# CH32F_V208C-R0.net
KiCad netlist of a schematic drawn in Altium Designer
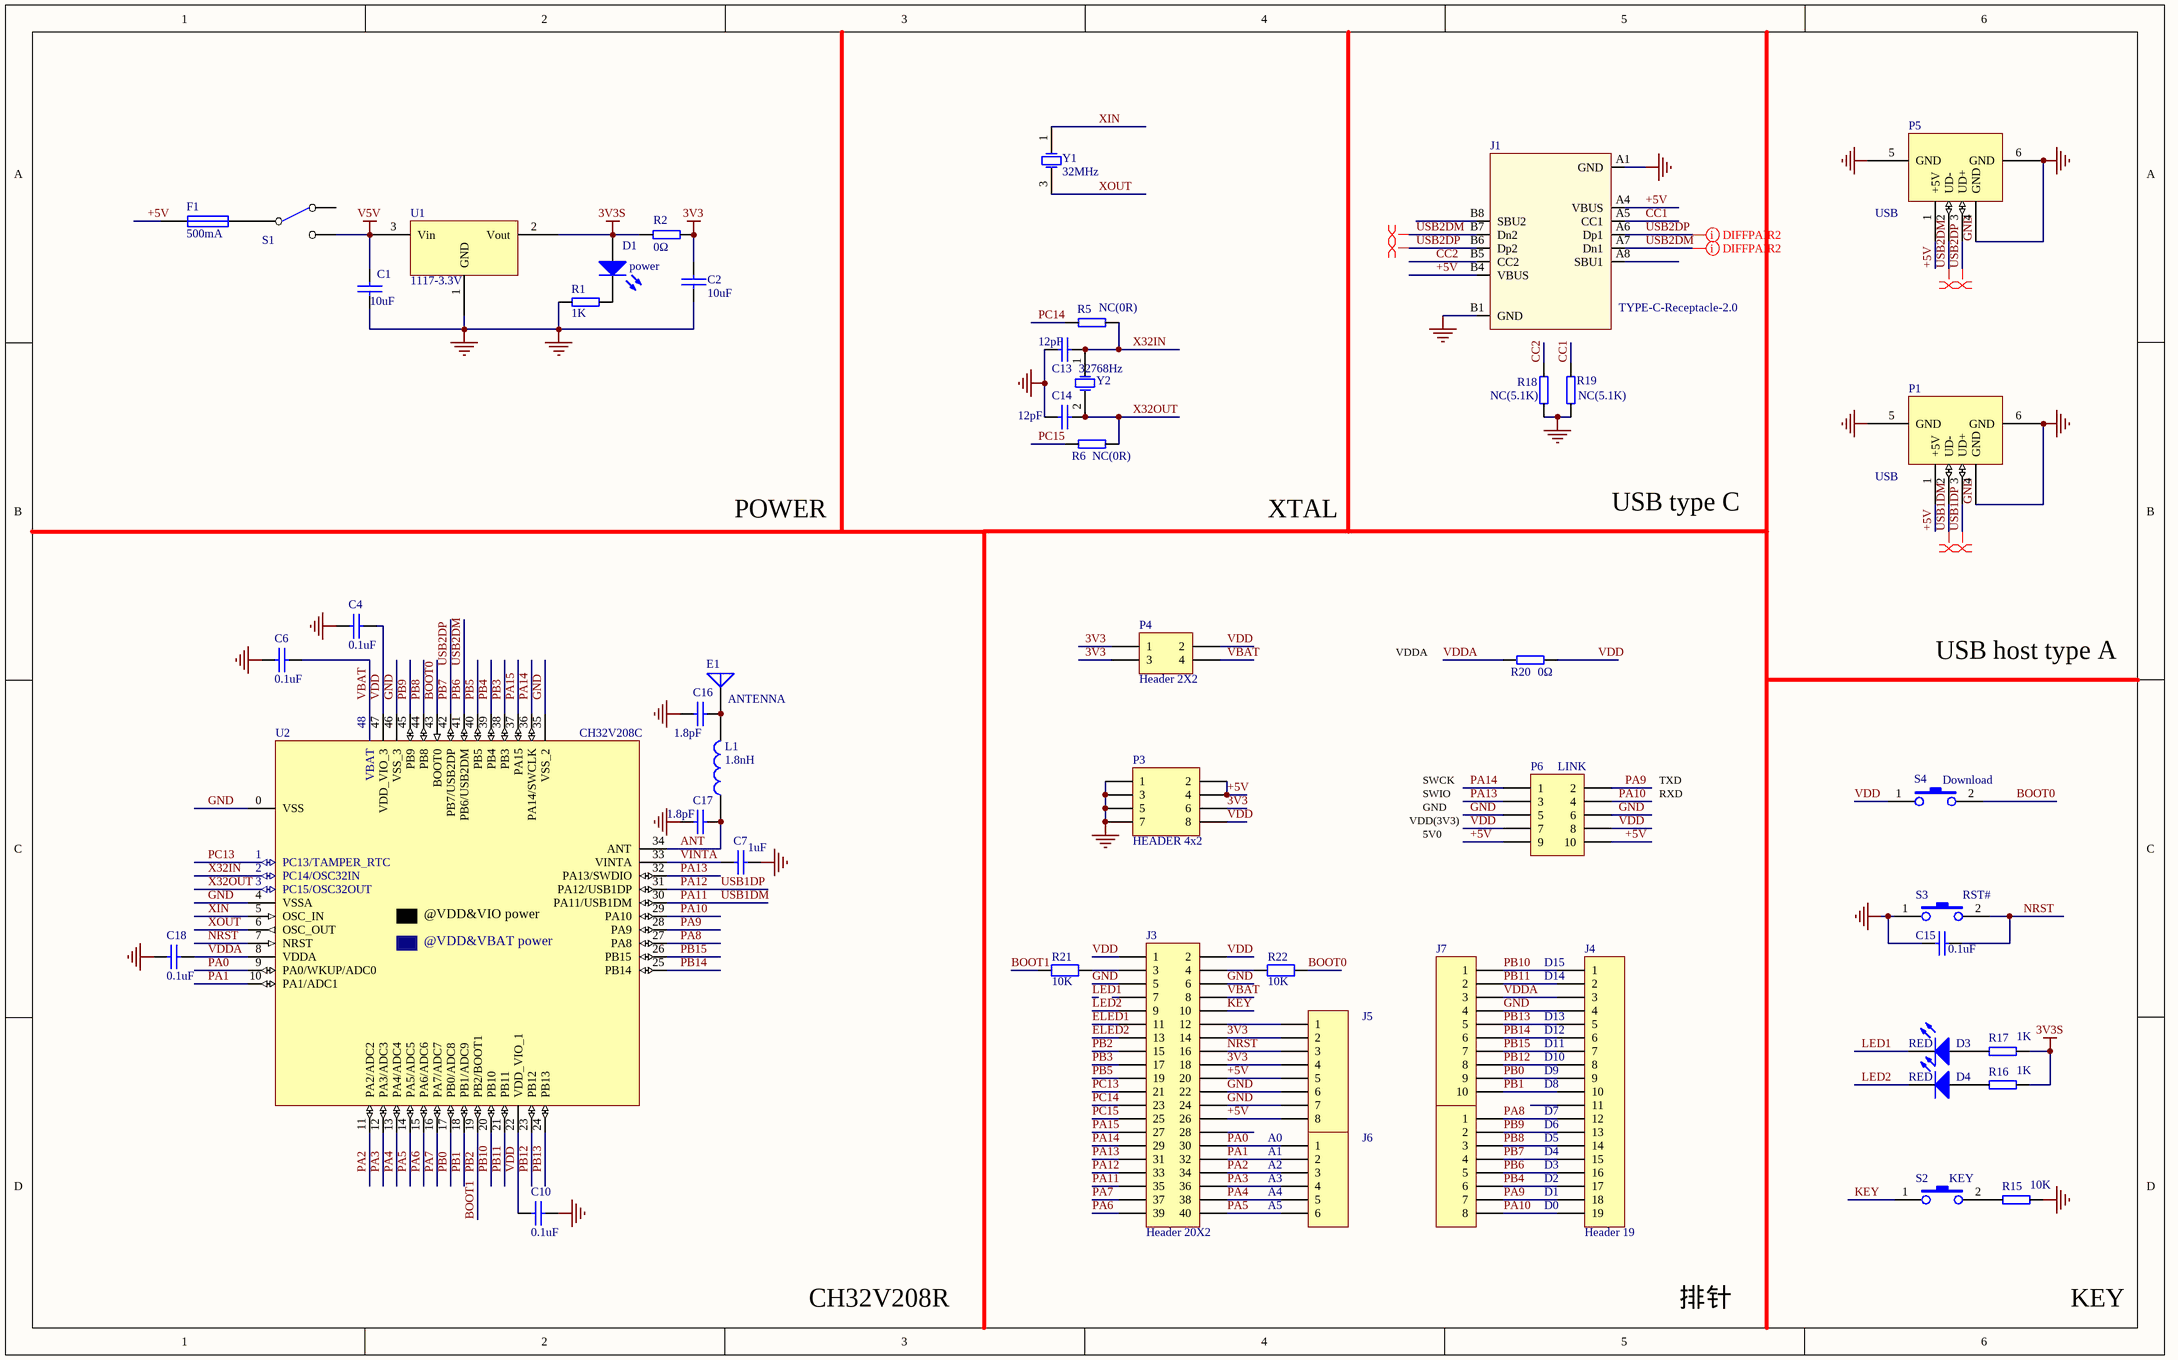
[diagram p0: CH32F&V208C-R0.SchDoc]

(export (version "E")
  (design (tool "Eeschema 10.0.6"))
  (components
    (comp (ref "C1")
      (value "10uF")
      (footprint "3216_C")
      (description "Capacitor")
      (libsource (lib "") (part "CAP_1"))
    )
    (comp (ref "C2")
      (value "10uF")
      (footprint "0603_C")
      (description "Capacitor")
      (libsource (lib "") (part "CAP_1"))
    )
    (comp (ref "C4")
      (value "0.1uF")
      (footprint "0603_C")
      (description "Capacitor")
      (libsource (lib "*") (part "CAP"))
    )
    (comp (ref "C6")
      (value "0.1uF")
      (footprint "0603_C")
      (description "Capacitor")
      (libsource (lib "*") (part "CAP"))
    )
    (comp (ref "C7")
      (value "1uF")
      (footprint "0603_C")
      (description "Capacitor")
      (libsource (lib "*") (part "CAP"))
    )
    (comp (ref "C10")
      (value "0.1uF")
      (footprint "0603_C")
      (description "Capacitor")
      (libsource (lib "*") (part "CAP"))
    )
    (comp (ref "C13")
      (value "12pF")
      (footprint "0603_C")
      (description "Capacitor")
      (libsource (lib "") (part "CAP_1"))
    )
    (comp (ref "C14")
      (value "12pF")
      (footprint "0603_C")
      (description "Capacitor")
      (libsource (lib "") (part "CAP_1"))
    )
    (comp (ref "C15")
      (value "0.1uF")
      (footprint "0603_C")
      (description "Capacitor")
      (libsource (lib "*") (part "CAP"))
    )
    (comp (ref "C16")
      (value "1.8pF")
      (footprint "0603_C")
      (description "Capacitor")
      (libsource (lib "*") (part "CAP"))
    )
    (comp (ref "C17")
      (value "1.8pF")
      (footprint "0603_C")
      (description "Capacitor")
      (libsource (lib "*") (part "CAP"))
    )
    (comp (ref "C18")
      (value "0.1uF")
      (footprint "0603_C")
      (description "Capacitor")
      (libsource (lib "*") (part "CAP"))
    )
    (comp (ref "D1")
      (value "power")
      (footprint "0603+")
      (description "Typical INFRARED GaAs LED")
      (fields (field (name "PUBLISHER") "Altium Limited"))
      (libsource (lib "*") (part "LED0"))
    )
    (comp (ref "D3")
      (value "RED")
      (footprint "0603+")
      (description "Typical INFRARED GaAs LED")
      (fields (field (name "PUBLISHER") "Altium Limited"))
      (libsource (lib "*") (part "LED0"))
    )
    (comp (ref "D4")
      (value "RED")
      (footprint "0603+")
      (description "Typical INFRARED GaAs LED")
      (fields (field (name "PUBLISHER") "Altium Limited"))
      (libsource (lib "*") (part "LED0"))
    )
    (comp (ref "E1")
      (value "ANTENNA")
      (footprint "ANT-F-1-2.4G-1.6mmFR4")
      (description "Generic Antenna")
      (libsource (lib "*") (part "ANTENNA"))
    )
    (comp (ref "F1")
      (value "500mA")
      (footprint "0603")
      (description "Fuse")
      (libsource (lib "wch_sch_others") (part "FUSE1"))
    )
    (comp (ref "J1")
      (value "TYPE-C-Receptacle-2.0")
      (footprint "TYPE-C-Receptacle-2.0")
      (description "Type-C USB2.0 母座")
      (libsource (lib "Miscellaneous SCH Lib") (part "TYPE-C-Receptacle-2.0"))
    )
    (comp (ref "J3")
      (value "Header 20X2")
      (footprint "IDC40-2.54mm")
      (description "Header, 20-Pin, Dual row")
      (fields (field (name "PUBLISHER") "Altium Limited"))
      (libsource (lib "Miscellaneous Connectors") (part "Header 20X2"))
    )
    (comp (ref "J4")
      (value "Header 19")
      (footprint "SIP19-2.54mm")
      (description "Header, 19-Pin")
      (fields (field (name "PUBLISHER") "Altium Limited"))
      (libsource (lib "Miscellaneous Connectors") (part "Header 19"))
    )
    (comp (ref "J5")
      (value "Header 8")
      (footprint "SIP8-2.54mm")
      (description "Header, 8-Pin")
      (fields (field (name "PUBLISHER") "Altium Limited"))
      (libsource (lib "Miscellaneous Connectors") (part "Header 8"))
    )
    (comp (ref "J6")
      (value "Header 6")
      (footprint "SIP6-2.54MM")
      (description "Header, 6-Pin")
      (fields (field (name "PUBLISHER") "Altium Limited"))
      (libsource (lib "Miscellaneous Connectors") (part "Header 6"))
    )
    (comp (ref "J7")
      (value "Header 10")
      (footprint "SIP10-2.54mm")
      (description "Header, 10-Pin")
      (fields (field (name "PUBLISHER") "Altium Limited"))
      (libsource (lib "Miscellaneous Connectors") (part "Header 10"))
    )
    (comp (ref "J8")
      (value "Header 8")
      (footprint "SIP8-2.54mm")
      (description "Header, 8-Pin")
      (fields (field (name "PUBLISHER") "Altium Limited"))
      (libsource (lib "") (part "Header 8_1"))
    )
    (comp (ref "L1") (value "1.8nH") (footprint "0603") (libsource (lib "*") (part "INDUCTOR")))
    (comp (ref "P1")
      (value "USB")
      (footprint "USBAF")
      (description "USB Port")
      (libsource (lib "*") (part "USB"))
    )
    (comp (ref "P3")
      (value "HEADER 4x2")
      (footprint "MYPCB:IDC8-2.54mm")
      (description "Header, 4-Pin, Dual row")
      (libsource (lib "wch_sch_others") (part "HEADER 4x2"))
    )
    (comp (ref "P4")
      (value "Header 2X2")
      (footprint "IDC4-2.54mm")
      (description "Header, 2-Pin, Dual row")
      (fields (field (name "PUBLISHER") "Altium Limited"))
      (libsource (lib "Miscellaneous Connectors") (part "Header 2X2"))
    )
    (comp (ref "P5")
      (value "USB")
      (footprint "USBAF")
      (description "USB Port")
      (libsource (lib "*") (part "USB"))
    )
    (comp (ref "P6")
      (value "LINK")
      (footprint "IDC10-2.54mm")
      (description "Header, 5-Pin, Dual row, Right Angle")
      (fields (field (name "PUBLISHER") "Altium Limited"))
      (libsource (lib "Miscellaneous Connectors") (part "Header 5X2H"))
    )
    (comp (ref "R1") (value "1K") (footprint "0603") (libsource (lib "wch_sch_others") (part "RES")))
    (comp (ref "R2") (value "0Ω") (footprint "0603") (libsource (lib "wch_sch_others") (part "RES")))
    (comp (ref "R5") (value "NC(0R)") (footprint "0603") (libsource (lib "wch_sch_others") (part "RES")))
    (comp (ref "R6") (value "NC(0R)") (footprint "0603") (libsource (lib "wch_sch_others") (part "RES")))
    (comp (ref "R15") (value "10K") (footprint "0603") (libsource (lib "wch_sch_others") (part "RES")))
    (comp (ref "R16") (value "1K") (footprint "0603") (libsource (lib "wch_sch_others") (part "RES")))
    (comp (ref "R17") (value "1K") (footprint "0603") (libsource (lib "wch_sch_others") (part "RES")))
    (comp (ref "R18") (value "NC(5.1K)") (footprint "0603") (libsource (lib "wch_sch_others") (part "RES")))
    (comp (ref "R19") (value "NC(5.1K)") (footprint "0603") (libsource (lib "wch_sch_others") (part "RES")))
    (comp (ref "R20") (value "0Ω") (footprint "0603") (libsource (lib "*") (part "R")))
    (comp (ref "R21")
      (value "10K")
      (footprint "0603")
      (description "Resistor")
      (libsource (lib "Miscellaneous Devices") (part "Res2"))
    )
    (comp (ref "R22")
      (value "10K")
      (footprint "0603")
      (description "Resistor")
      (libsource (lib "Miscellaneous Devices") (part "Res2"))
    )
    (comp (ref "S1") (value "SW SPDT") (footprint "SW1") (libsource (lib "*") (part "SW SPDT")))
    (comp (ref "S2")
      (value "KEY")
      (footprint "SMD_6.1x3.65x2.5mm-KEY")
      (libsource (lib "wch_sch_others") (part "KEY1"))
    )
    (comp (ref "S3")
      (value "RST#")
      (footprint "SMD_6.1x3.65x2.5mm-KEY")
      (libsource (lib "wch_sch_others") (part "KEY1"))
    )
    (comp (ref "S4")
      (value "Download")
      (footprint "SMD_6.1x3.65x2.5mm-KEY")
      (libsource (lib "wch_sch_others") (part "KEY1"))
    )
    (comp (ref "U1")
      (value "1117-3.3V")
      (footprint "SOT-223")
      (libsource (lib "wch_sch_others") (part "1117-3.3V"))
    )
    (comp (ref "U2")
      (value "CH32V208C")
      (footprint "QFN48_5x5")
      (description "RISC-V BLE5.3 MCU, 10M Ethernet, 2*USB, CAN")
      (libsource (lib "CHXXX") (part "CH32V208C"))
    )
    (comp (ref "Y1")
      (value "32MHz")
      (footprint "XT3225")
      (description "Crystal Oscillator")
      (fields (field (name "PUBLISHER") "Altium Limited"))
      (libsource (lib "") (part "XTAL_1"))
    )
    (comp (ref "Y2")
      (value "32768Hz")
      (footprint "FC-135")
      (description "Crystal Oscillator")
      (fields (field (name "PUBLISHER") "Altium Limited"))
      (libsource (lib "*") (part "XTAL"))
    )
  )
  (nets
    (net (code "1") (name "/+5V") (class "Default")
      (node (ref "F1") (pin "1") (pinfunction "1_1") (pintype "passive"))
      (node (ref "J1") (pin "A4") (pinfunction "VBUS_A4") (pintype "passive"))
      (node (ref "J1") (pin "B4") (pinfunction "VBUS_B4") (pintype "passive"))
      (node (ref "J3") (pin "20") (pinfunction "20_20") (pintype "passive"))
      (node (ref "J3") (pin "26") (pinfunction "26_26") (pintype "passive"))
      (node (ref "J5") (pin "5") (pinfunction "5_5") (pintype "passive"))
      (node (ref "J5") (pin "8") (pinfunction "8_8") (pintype "passive"))
      (node (ref "P1") (pin "1") (pinfunction "+5V_1") (pintype "power_in"))
      (node (ref "P3") (pin "2") (pinfunction "2_2") (pintype "passive"))
      (node (ref "P3") (pin "4") (pinfunction "4_4") (pintype "passive"))
      (node (ref "P5") (pin "1") (pinfunction "+5V_1") (pintype "power_in"))
      (node (ref "P6") (pin "10") (pinfunction "10_10") (pintype "passive"))
      (node (ref "P6") (pin "9") (pinfunction "9_9") (pintype "passive"))
    )
    (net (code "2") (name "/ANT") (class "Default")
      (node (ref "C17") (pin "2") (pinfunction "2_2") (pintype "passive"))
      (node (ref "L1") (pin "1") (pinfunction "1_1") (pintype "passive"))
      (node (ref "U2") (pin "34") (pinfunction "ANT_34") (pintype "power_in"))
    )
    (net (code "3") (name "/BOOT0") (class "Default")
      (node (ref "R22") (pin "2") (pinfunction "2_2") (pintype "passive"))
      (node (ref "S4") (pin "2") (pinfunction "2_2") (pintype "passive"))
      (node (ref "U2") (pin "43") (pinfunction "BOOT0_43") (pintype "input"))
    )
    (net (code "4") (name "/BOOT1") (class "Default")
      (node (ref "J3") (pin "15") (pinfunction "15_15") (pintype "passive"))
      (node (ref "R21") (pin "1") (pinfunction "1_1") (pintype "passive"))
      (node (ref "U2") (pin "19") (pinfunction "PB2/BOOT1_19") (pintype "bidirectional"))
    )
    (net (code "5") (name "/CC1") (class "Default")
      (node (ref "J1") (pin "A5") (pinfunction "CC1_A5") (pintype "passive"))
      (node (ref "R19") (pin "1") (pintype "passive"))
    )
    (net (code "6") (name "/CC2") (class "Default")
      (node (ref "J1") (pin "B5") (pinfunction "CC2_B5") (pintype "passive"))
      (node (ref "R18") (pin "1") (pintype "passive"))
    )
    (net (code "7") (name "/ELED1") (class "Default")
      (node (ref "J3") (pin "11") (pinfunction "11_11") (pintype "passive"))
    )
    (net (code "8") (name "/ELED2") (class "Default")
      (node (ref "J3") (pin "13") (pinfunction "13_13") (pintype "passive"))
    )
    (net (code "9") (name "/KEY") (class "Default")
      (node (ref "J3") (pin "10") (pinfunction "10_10") (pintype "passive"))
      (node (ref "S2") (pin "1") (pinfunction "1_1") (pintype "passive"))
    )
    (net (code "10") (name "/LED1") (class "Default")
      (node (ref "D3") (pin "2") (pinfunction "K_2") (pintype "passive"))
    )
    (net (code "11") (name "/LED2") (class "Default")
      (node (ref "D4") (pin "2") (pinfunction "K_2") (pintype "passive"))
      (node (ref "J3") (pin "9") (pinfunction "9_9") (pintype "passive"))
    )
    (net (code "12") (name "/NRST") (class "Default")
      (node (ref "C15") (pin "2") (pinfunction "2_2") (pintype "passive"))
      (node (ref "J3") (pin "16") (pinfunction "16_16") (pintype "passive"))
      (node (ref "J5") (pin "3") (pinfunction "3_3") (pintype "passive"))
      (node (ref "S3") (pin "2") (pinfunction "2_2") (pintype "passive"))
      (node (ref "U2") (pin "7") (pinfunction "NRST_7") (pintype "input"))
    )
    (net (code "13") (name "/PA0") (class "Default")
      (node (ref "J3") (pin "30") (pinfunction "30_30") (pintype "passive"))
      (node (ref "J6") (pin "1") (pinfunction "1_1") (pintype "passive"))
      (node (ref "U2") (pin "9") (pinfunction "PA0/WKUP/ADC0_9") (pintype "bidirectional"))
    )
    (net (code "14") (name "/PA1") (class "Default")
      (node (ref "J3") (pin "32") (pinfunction "32_32") (pintype "passive"))
      (node (ref "J6") (pin "2") (pinfunction "2_2") (pintype "passive"))
      (node (ref "U2") (pin "10") (pinfunction "PA1/ADC1_10") (pintype "bidirectional"))
    )
    (net (code "15") (name "/PA2") (class "Default")
      (node (ref "J3") (pin "34") (pinfunction "34_34") (pintype "passive"))
      (node (ref "J6") (pin "3") (pinfunction "3_3") (pintype "passive"))
      (node (ref "U2") (pin "11") (pinfunction "PA2/ADC2_11") (pintype "bidirectional"))
    )
    (net (code "16") (name "/PA3") (class "Default")
      (node (ref "J3") (pin "36") (pinfunction "36_36") (pintype "passive"))
      (node (ref "J6") (pin "4") (pinfunction "4_4") (pintype "passive"))
      (node (ref "U2") (pin "12") (pinfunction "PA3/ADC3_12") (pintype "bidirectional"))
    )
    (net (code "17") (name "/PA4") (class "Default")
      (node (ref "J3") (pin "38") (pinfunction "38_38") (pintype "passive"))
      (node (ref "J6") (pin "5") (pinfunction "5_5") (pintype "passive"))
      (node (ref "U2") (pin "13") (pinfunction "PA4/ADC4_13") (pintype "bidirectional"))
    )
    (net (code "18") (name "/PA5") (class "Default")
      (node (ref "J3") (pin "40") (pinfunction "40_40") (pintype "passive"))
      (node (ref "J6") (pin "6") (pinfunction "6_6") (pintype "passive"))
      (node (ref "U2") (pin "14") (pinfunction "PA5/ADC5_14") (pintype "bidirectional"))
    )
    (net (code "19") (name "/PA6") (class "Default")
      (node (ref "J3") (pin "39") (pinfunction "39_39") (pintype "passive"))
      (node (ref "U2") (pin "15") (pinfunction "PA6/ADC6_15") (pintype "bidirectional"))
    )
    (net (code "20") (name "/PA7") (class "Default")
      (node (ref "J3") (pin "37") (pinfunction "37_37") (pintype "passive"))
      (node (ref "U2") (pin "16") (pinfunction "PA7/ADC7_16") (pintype "bidirectional"))
    )
    (net (code "21") (name "/PA8") (class "Default")
      (node (ref "J4") (pin "12") (pinfunction "12_12") (pintype "passive"))
      (node (ref "J8") (pin "1") (pinfunction "1_1") (pintype "passive"))
      (node (ref "U2") (pin "27") (pinfunction "PA8_27") (pintype "bidirectional"))
    )
    (net (code "22") (name "/PA9") (class "Default")
      (node (ref "J4") (pin "18") (pinfunction "18_18") (pintype "passive"))
      (node (ref "J8") (pin "7") (pinfunction "7_7") (pintype "passive"))
      (node (ref "P6") (pin "2") (pinfunction "2_2") (pintype "passive"))
      (node (ref "U2") (pin "28") (pinfunction "PA9_28") (pintype "bidirectional"))
    )
    (net (code "23") (name "/PA10") (class "Default")
      (node (ref "J4") (pin "19") (pinfunction "19_19") (pintype "passive"))
      (node (ref "J8") (pin "8") (pinfunction "8_8") (pintype "passive"))
      (node (ref "P6") (pin "4") (pinfunction "4_4") (pintype "passive"))
      (node (ref "U2") (pin "29") (pinfunction "PA10_29") (pintype "bidirectional"))
    )
    (net (code "24") (name "/PA11") (class "Default")
      (node (ref "J3") (pin "35") (pinfunction "35_35") (pintype "passive"))
      (node (ref "P1") (pin "2") (pinfunction "UD-_2") (pintype "bidirectional"))
      (node (ref "U2") (pin "30") (pinfunction "PA11/USB1DM_30") (pintype "bidirectional"))
    )
    (net (code "25") (name "/PA12") (class "Default")
      (node (ref "J3") (pin "33") (pinfunction "33_33") (pintype "passive"))
      (node (ref "P1") (pin "3") (pinfunction "UD+_3") (pintype "bidirectional"))
      (node (ref "U2") (pin "31") (pinfunction "PA12/USB1DP_31") (pintype "bidirectional"))
    )
    (net (code "26") (name "/PA13") (class "Default")
      (node (ref "J3") (pin "31") (pinfunction "31_31") (pintype "passive"))
      (node (ref "P6") (pin "3") (pinfunction "3_3") (pintype "passive"))
      (node (ref "U2") (pin "32") (pinfunction "PA13/SWDIO_32") (pintype "bidirectional"))
    )
    (net (code "27") (name "/PA14") (class "Default")
      (node (ref "J3") (pin "29") (pinfunction "29_29") (pintype "passive"))
      (node (ref "P6") (pin "1") (pinfunction "1_1") (pintype "passive"))
      (node (ref "U2") (pin "36") (pinfunction "PA14/SWCLK_36") (pintype "bidirectional"))
    )
    (net (code "28") (name "/PA15") (class "Default")
      (node (ref "J3") (pin "27") (pinfunction "27_27") (pintype "passive"))
      (node (ref "U2") (pin "37") (pinfunction "PA15_37") (pintype "bidirectional"))
    )
    (net (code "29") (name "/PB0") (class "Default")
      (node (ref "J4") (pin "9") (pinfunction "9_9") (pintype "passive"))
      (node (ref "J7") (pin "9") (pinfunction "9_9") (pintype "passive"))
      (node (ref "U2") (pin "17") (pinfunction "PB0/ADC8_17") (pintype "bidirectional"))
    )
    (net (code "30") (name "/PB1") (class "Default")
      (node (ref "J4") (pin "10") (pinfunction "10_10") (pintype "passive"))
      (node (ref "J7") (pin "10") (pinfunction "10_10") (pintype "passive"))
      (node (ref "U2") (pin "18") (pinfunction "PB1/ADC9_18") (pintype "bidirectional"))
    )
    (net (code "31") (name "/PB3") (class "Default")
      (node (ref "J3") (pin "17") (pinfunction "17_17") (pintype "passive"))
      (node (ref "U2") (pin "38") (pinfunction "PB3_38") (pintype "bidirectional"))
    )
    (net (code "32") (name "/PB4") (class "Default")
      (node (ref "J4") (pin "17") (pinfunction "17_17") (pintype "passive"))
      (node (ref "J8") (pin "6") (pinfunction "6_6") (pintype "passive"))
      (node (ref "U2") (pin "39") (pinfunction "PB4_39") (pintype "bidirectional"))
    )
    (net (code "33") (name "/PB5") (class "Default")
      (node (ref "J3") (pin "19") (pinfunction "19_19") (pintype "passive"))
      (node (ref "U2") (pin "40") (pinfunction "PB5_40") (pintype "bidirectional"))
    )
    (net (code "34") (name "/PB6") (class "Default")
      (node (ref "J1") (pin "A7") (pinfunction "Dn1_A7") (pintype "passive"))
      (node (ref "J1") (pin "B7") (pinfunction "Dn2_B7") (pintype "passive"))
      (node (ref "J4") (pin "16") (pinfunction "16_16") (pintype "passive"))
      (node (ref "J8") (pin "5") (pinfunction "5_5") (pintype "passive"))
      (node (ref "P5") (pin "2") (pinfunction "UD-_2") (pintype "bidirectional"))
      (node (ref "U2") (pin "41") (pinfunction "PB6/USB2DM_41") (pintype "bidirectional"))
    )
    (net (code "35") (name "/PB7") (class "Default")
      (node (ref "J1") (pin "A6") (pinfunction "Dp1_A6") (pintype "passive"))
      (node (ref "J1") (pin "B6") (pinfunction "Dp2_B6") (pintype "passive"))
      (node (ref "J4") (pin "15") (pinfunction "15_15") (pintype "passive"))
      (node (ref "J8") (pin "4") (pinfunction "4_4") (pintype "passive"))
      (node (ref "P5") (pin "3") (pinfunction "UD+_3") (pintype "bidirectional"))
      (node (ref "U2") (pin "42") (pinfunction "PB7/USB2DP_42") (pintype "bidirectional"))
    )
    (net (code "36") (name "/PB8") (class "Default")
      (node (ref "J4") (pin "14") (pinfunction "14_14") (pintype "passive"))
      (node (ref "J8") (pin "3") (pinfunction "3_3") (pintype "passive"))
      (node (ref "U2") (pin "44") (pinfunction "PB8_44") (pintype "bidirectional"))
    )
    (net (code "37") (name "/PB9") (class "Default")
      (node (ref "J4") (pin "13") (pinfunction "13_13") (pintype "passive"))
      (node (ref "J8") (pin "2") (pinfunction "2_2") (pintype "passive"))
      (node (ref "U2") (pin "45") (pinfunction "PB9_45") (pintype "bidirectional"))
    )
    (net (code "38") (name "/PB10") (class "Default")
      (node (ref "J4") (pin "1") (pinfunction "1_1") (pintype "passive"))
      (node (ref "J7") (pin "1") (pinfunction "1_1") (pintype "passive"))
      (node (ref "U2") (pin "20") (pinfunction "PB10_20") (pintype "bidirectional"))
    )
    (net (code "39") (name "/PB11") (class "Default")
      (node (ref "J4") (pin "2") (pinfunction "2_2") (pintype "passive"))
      (node (ref "J7") (pin "2") (pinfunction "2_2") (pintype "passive"))
      (node (ref "U2") (pin "21") (pinfunction "PB11_21") (pintype "bidirectional"))
    )
    (net (code "40") (name "/PB12") (class "Default")
      (node (ref "J4") (pin "8") (pinfunction "8_8") (pintype "passive"))
      (node (ref "J7") (pin "8") (pinfunction "8_8") (pintype "passive"))
      (node (ref "U2") (pin "23") (pinfunction "PB12_23") (pintype "bidirectional"))
    )
    (net (code "41") (name "/PB13") (class "Default")
      (node (ref "J4") (pin "5") (pinfunction "5_5") (pintype "passive"))
      (node (ref "J7") (pin "5") (pinfunction "5_5") (pintype "passive"))
      (node (ref "U2") (pin "24") (pinfunction "PB13_24") (pintype "bidirectional"))
    )
    (net (code "42") (name "/PB14") (class "Default")
      (node (ref "J4") (pin "6") (pinfunction "6_6") (pintype "passive"))
      (node (ref "J7") (pin "6") (pinfunction "6_6") (pintype "passive"))
      (node (ref "U2") (pin "25") (pinfunction "PB14_25") (pintype "bidirectional"))
    )
    (net (code "43") (name "/PB15") (class "Default")
      (node (ref "J4") (pin "7") (pinfunction "7_7") (pintype "passive"))
      (node (ref "J7") (pin "7") (pinfunction "7_7") (pintype "passive"))
      (node (ref "U2") (pin "26") (pinfunction "PB15_26") (pintype "bidirectional"))
    )
    (net (code "44") (name "/PC13") (class "Default")
      (node (ref "J3") (pin "21") (pinfunction "21_21") (pintype "passive"))
      (node (ref "U2") (pin "1") (pinfunction "PC13/TAMPER_RTC_1") (pintype "bidirectional"))
    )
    (net (code "45") (name "/PC14") (class "Default")
      (node (ref "J3") (pin "23") (pinfunction "23_23") (pintype "passive"))
      (node (ref "R5") (pin "1") (pintype "passive"))
    )
    (net (code "46") (name "/PC15") (class "Default")
      (node (ref "J3") (pin "25") (pinfunction "25_25") (pintype "passive"))
      (node (ref "R6") (pin "1") (pintype "passive"))
    )
    (net (code "47") (name "/VBAT") (class "Default")
      (node (ref "C6") (pin "1") (pinfunction "1_1") (pintype "passive"))
      (node (ref "J3") (pin "8") (pinfunction "8_8") (pintype "passive"))
      (node (ref "P4") (pin "4") (pinfunction "4_4") (pintype "passive"))
      (node (ref "U2") (pin "48") (pinfunction "VBAT_48") (pintype "power_in"))
    )
    (net (code "48") (name "/VDD") (class "Default")
      (node (ref "C10") (pin "2") (pinfunction "2_2") (pintype "passive"))
      (node (ref "C4") (pin "1") (pinfunction "1_1") (pintype "passive"))
      (node (ref "J3") (pin "1") (pinfunction "1_1") (pintype "passive"))
      (node (ref "J3") (pin "2") (pinfunction "2_2") (pintype "passive"))
      (node (ref "P3") (pin "8") (pinfunction "8_8") (pintype "passive"))
      (node (ref "P4") (pin "2") (pinfunction "2_2") (pintype "passive"))
      (node (ref "P6") (pin "7") (pinfunction "7_7") (pintype "passive"))
      (node (ref "P6") (pin "8") (pinfunction "8_8") (pintype "passive"))
      (node (ref "R20") (pin "1") (pinfunction "1_1") (pintype "passive"))
      (node (ref "S4") (pin "1") (pinfunction "1_1") (pintype "passive"))
      (node (ref "U2") (pin "22") (pinfunction "VDD_VIO_1_22") (pintype "power_in"))
      (node (ref "U2") (pin "47") (pinfunction "VDD_VIO_3_47") (pintype "power_in"))
    )
    (net (code "49") (name "/VDDA") (class "Default")
      (node (ref "C18") (pin "1") (pinfunction "1_1") (pintype "passive"))
      (node (ref "J4") (pin "3") (pinfunction "3_3") (pintype "passive"))
      (node (ref "J7") (pin "3") (pinfunction "3_3") (pintype "passive"))
      (node (ref "R20") (pin "2") (pinfunction "2_2") (pintype "passive"))
      (node (ref "U2") (pin "8") (pinfunction "VDDA_8") (pintype "power_in"))
    )
    (net (code "50") (name "/VINTA") (class "Default")
      (node (ref "C7") (pin "1") (pinfunction "1_1") (pintype "passive"))
      (node (ref "U2") (pin "33") (pinfunction "VINTA_33") (pintype "power_in"))
    )
    (net (code "51") (name "/X32IN") (class "Default")
      (node (ref "C13") (pin "2") (pinfunction "2_2") (pintype "passive"))
      (node (ref "R5") (pin "2") (pintype "passive"))
      (node (ref "U2") (pin "2") (pinfunction "PC14/OSC32IN_2") (pintype "bidirectional"))
      (node (ref "Y2") (pin "1") (pinfunction "OSC1_1") (pintype "passive"))
    )
    (net (code "52") (name "/X32OUT") (class "Default")
      (node (ref "C14") (pin "2") (pinfunction "2_2") (pintype "passive"))
      (node (ref "R6") (pin "2") (pintype "passive"))
      (node (ref "U2") (pin "3") (pinfunction "PC15/OSC32OUT_3") (pintype "bidirectional"))
      (node (ref "Y2") (pin "2") (pinfunction "OSC2_2") (pintype "passive"))
    )
    (net (code "53") (name "/XIN") (class "Default")
      (node (ref "U2") (pin "5") (pinfunction "OSC_IN_5") (pintype "input"))
      (node (ref "Y1") (pin "1") (pinfunction "OSC1_1") (pintype "passive"))
    )
    (net (code "54") (name "/XOUT") (class "Default")
      (node (ref "U2") (pin "6") (pinfunction "OSC_OUT_6") (pintype "output"))
      (node (ref "Y1") (pin "3") (pinfunction "OSC2_3") (pintype "passive"))
    )
    (net (code "55") (name "3V3") (class "Default")
      (node (ref "C2") (pin "1") (pinfunction "1_1") (pintype "passive"))
      (node (ref "J3") (pin "14") (pinfunction "14_14") (pintype "passive"))
      (node (ref "J3") (pin "18") (pinfunction "18_18") (pintype "passive"))
      (node (ref "J5") (pin "2") (pinfunction "2_2") (pintype "passive"))
      (node (ref "J5") (pin "4") (pinfunction "4_4") (pintype "passive"))
      (node (ref "P3") (pin "6") (pinfunction "6_6") (pintype "passive"))
      (node (ref "P4") (pin "1") (pinfunction "1_1") (pintype "passive"))
      (node (ref "P4") (pin "3") (pinfunction "3_3") (pintype "passive"))
      (node (ref "R2") (pin "1") (pintype "passive"))
    )
    (net (code "56") (name "3V3S") (class "Default")
      (node (ref "D1") (pin "1") (pinfunction "A_1") (pintype "passive"))
      (node (ref "R16") (pin "1") (pintype "passive"))
      (node (ref "R17") (pin "1") (pintype "passive"))
      (node (ref "R2") (pin "2") (pintype "passive"))
      (node (ref "U1") (pin "2") (pinfunction "Vout_2") (pintype "passive"))
    )
    (net (code "57") (name "GND") (class "Default")
      (node (ref "C1") (pin "2") (pinfunction "2_2") (pintype "passive"))
      (node (ref "C10") (pin "1") (pinfunction "1_1") (pintype "passive"))
      (node (ref "C13") (pin "1") (pinfunction "1_1") (pintype "passive"))
      (node (ref "C14") (pin "1") (pinfunction "1_1") (pintype "passive"))
      (node (ref "C15") (pin "1") (pinfunction "1_1") (pintype "passive"))
      (node (ref "C16") (pin "1") (pinfunction "1_1") (pintype "passive"))
      (node (ref "C17") (pin "1") (pinfunction "1_1") (pintype "passive"))
      (node (ref "C18") (pin "2") (pinfunction "2_2") (pintype "passive"))
      (node (ref "C2") (pin "2") (pinfunction "2_2") (pintype "passive"))
      (node (ref "C4") (pin "2") (pinfunction "2_2") (pintype "passive"))
      (node (ref "C6") (pin "2") (pinfunction "2_2") (pintype "passive"))
      (node (ref "C7") (pin "2") (pinfunction "2_2") (pintype "passive"))
      (node (ref "J1") (pin "A1") (pinfunction "GND_A1") (pintype "passive"))
      (node (ref "J1") (pin "B1") (pinfunction "GND_B1") (pintype "passive"))
      (node (ref "J3") (pin "22") (pinfunction "22_22") (pintype "passive"))
      (node (ref "J3") (pin "24") (pinfunction "24_24") (pintype "passive"))
      (node (ref "J3") (pin "5") (pinfunction "5_5") (pintype "passive"))
      (node (ref "J3") (pin "6") (pinfunction "6_6") (pintype "passive"))
      (node (ref "J4") (pin "4") (pinfunction "4_4") (pintype "passive"))
      (node (ref "J5") (pin "6") (pinfunction "6_6") (pintype "passive"))
      (node (ref "J5") (pin "7") (pinfunction "7_7") (pintype "passive"))
      (node (ref "J7") (pin "4") (pinfunction "4_4") (pintype "passive"))
      (node (ref "P1") (pin "4") (pinfunction "GND_4") (pintype "power_in"))
      (node (ref "P1") (pin "5") (pinfunction "GND_5") (pintype "power_in"))
      (node (ref "P1") (pin "6") (pinfunction "GND_6") (pintype "power_in"))
      (node (ref "P3") (pin "1") (pinfunction "1_1") (pintype "passive"))
      (node (ref "P3") (pin "3") (pinfunction "3_3") (pintype "passive"))
      (node (ref "P3") (pin "5") (pinfunction "5_5") (pintype "passive"))
      (node (ref "P3") (pin "7") (pinfunction "7_7") (pintype "passive"))
      (node (ref "P5") (pin "4") (pinfunction "GND_4") (pintype "power_in"))
      (node (ref "P5") (pin "5") (pinfunction "GND_5") (pintype "power_in"))
      (node (ref "P5") (pin "6") (pinfunction "GND_6") (pintype "power_in"))
      (node (ref "P6") (pin "5") (pinfunction "5_5") (pintype "passive"))
      (node (ref "P6") (pin "6") (pinfunction "6_6") (pintype "passive"))
      (node (ref "R1") (pin "1") (pintype "passive"))
      (node (ref "R15") (pin "1") (pintype "passive"))
      (node (ref "R18") (pin "2") (pintype "passive"))
      (node (ref "R19") (pin "2") (pintype "passive"))
      (node (ref "S3") (pin "1") (pinfunction "1_1") (pintype "passive"))
      (node (ref "U1") (pin "1") (pinfunction "GND_1") (pintype "passive"))
      (node (ref "U2") (pin "0") (pinfunction "VSS_0") (pintype "power_in"))
      (node (ref "U2") (pin "35") (pinfunction "VSS_2_35") (pintype "power_in"))
      (node (ref "U2") (pin "4") (pinfunction "VSSA_4") (pintype "power_in"))
      (node (ref "U2") (pin "46") (pinfunction "VSS_3_46") (pintype "power_in"))
    )
    (net (code "58") (name "Net-(D1-K)") (class "Default")
      (node (ref "D1") (pin "2") (pinfunction "K_2") (pintype "passive"))
      (node (ref "R1") (pin "2") (pintype "passive"))
    )
    (net (code "59") (name "Net-(D3-A)") (class "Default")
      (node (ref "D3") (pin "1") (pinfunction "A_1") (pintype "passive"))
      (node (ref "R17") (pin "2") (pintype "passive"))
    )
    (net (code "60") (name "Net-(D4-A)") (class "Default")
      (node (ref "D4") (pin "1") (pinfunction "A_1") (pintype "passive"))
      (node (ref "R16") (pin "2") (pintype "passive"))
    )
    (net (code "61") (name "Net-(E1-A)") (class "Default")
      (node (ref "C16") (pin "2") (pinfunction "2_2") (pintype "passive"))
      (node (ref "E1") (pin "1") (pinfunction "A_1") (pintype "passive"))
      (node (ref "L1") (pin "2") (pinfunction "2_2") (pintype "passive"))
    )
    (net (code "62") (name "Net-(J3-Pad3)") (class "Default")
      (node (ref "J3") (pin "3") (pinfunction "3_3") (pintype "passive"))
      (node (ref "R21") (pin "2") (pinfunction "2_2") (pintype "passive"))
    )
    (net (code "63") (name "Net-(J3-Pad4)") (class "Default")
      (node (ref "J3") (pin "4") (pinfunction "4_4") (pintype "passive"))
      (node (ref "R22") (pin "1") (pinfunction "1_1") (pintype "passive"))
    )
    (net (code "64") (name "Net-(J3-Pad12)") (class "Default")
      (node (ref "J3") (pin "12") (pinfunction "12_12") (pintype "passive"))
      (node (ref "J5") (pin "1") (pinfunction "1_1") (pintype "passive"))
    )
    (net (code "65") (name "Net-(R15-Pad2)") (class "Default")
      (node (ref "R15") (pin "2") (pintype "passive"))
      (node (ref "S2") (pin "2") (pinfunction "2_2") (pintype "passive"))
    )
    (net (code "66") (name "Net-(S1-COMMON)") (class "Default")
      (node (ref "F1") (pin "2") (pinfunction "2_2") (pintype "passive"))
      (node (ref "S1") (pin "1") (pinfunction "COMMON_1") (pintype "passive"))
    )
    (net (code "67") (name "V5V") (class "Default")
      (node (ref "C1") (pin "1") (pinfunction "1_1") (pintype "passive"))
      (node (ref "S1") (pin "2") (pinfunction "NC_2") (pintype "passive"))
      (node (ref "U1") (pin "3") (pinfunction "Vin_3") (pintype "passive"))
    )
    (net (code "68") (name "unconnected-(J1-SBU1-PadA8)") (class "Default")
      (node (ref "J1") (pin "A8") (pinfunction "SBU1_A8") (pintype "passive"))
    )
    (net (code "69") (name "unconnected-(J1-SBU2-PadB8)") (class "Default")
      (node (ref "J1") (pin "B8") (pinfunction "SBU2_B8") (pintype "passive"))
    )
    (net (code "70") (name "unconnected-(J3-Pad7)") (class "Default")
      (node (ref "J3") (pin "7") (pinfunction "7_7") (pintype "passive"))
    )
    (net (code "71") (name "unconnected-(J3-Pad28)") (class "Default")
      (node (ref "J3") (pin "28") (pinfunction "28_28") (pintype "passive"))
    )
    (net (code "72") (name "unconnected-(J4-Pad11)") (class "Default")
      (node (ref "J4") (pin "11") (pinfunction "11_11") (pintype "passive"))
    )
    (net (code "73") (name "unconnected-(S1-NO-Pad3)") (class "Default")
      (node (ref "S1") (pin "3") (pinfunction "NO_3") (pintype "passive"))
    )
  )
)
